# mcu.net
KiCad netlist of a schematic drawn in Altium Designer
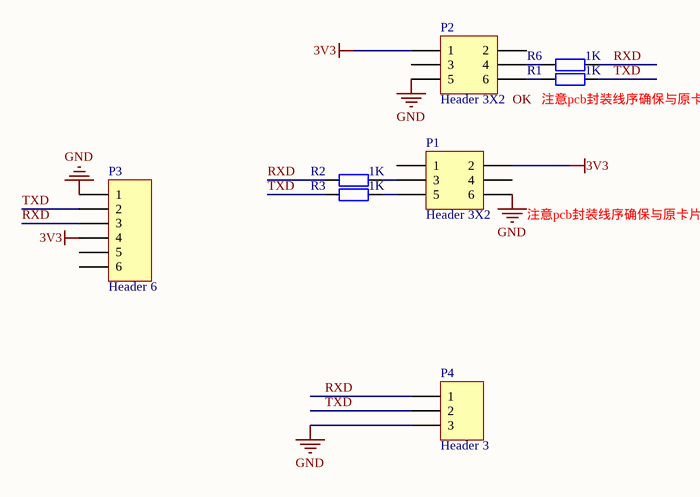
[diagram p0: mcu.SchDoc]

(export (version "E")
  (design (tool "Eeschema 10.0.6"))
  (components
    (comp (ref "P1")
      (value "Header 3X2")
      (footprint "3x2X2MM")
      (description "Header, 3-Pin, Dual row")
      (fields (field (name "PUBLISHER") "Altium Limited"))
      (libsource (lib "Miscellaneous Connectors") (part "Header 3X2"))
    )
    (comp (ref "P2")
      (value "Header 3X2")
      (footprint "3x2X2MM")
      (description "Header, 3-Pin, Dual row")
      (fields (field (name "PUBLISHER") "Altium Limited"))
      (libsource (lib "Miscellaneous Connectors") (part "Header 3X2"))
    )
    (comp (ref "P3")
      (value "Header 6")
      (footprint "5X2MMZ")
      (description "Header, 6-Pin")
      (fields (field (name "PUBLISHER") "Altium Limited"))
      (libsource (lib "Miscellaneous Connectors") (part "Header 6"))
    )
    (comp (ref "P4")
      (value "Header 3")
      (footprint "HDR1X3")
      (description "Header, 3-Pin")
      (fields (field (name "PUBLISHER") "Altium Limited"))
      (libsource (lib "Miscellaneous Connectors") (part "Header 3"))
    )
    (comp (ref "R1")
      (value "1K")
      (footprint "0603R")
      (description "Resistor")
      (fields (field (name "PUBLISHER") "Altium Limited"))
      (libsource (lib "Miscellaneous Devices") (part "Res2"))
    )
    (comp (ref "R2")
      (value "1K")
      (footprint "0603R")
      (description "Resistor")
      (fields (field (name "PUBLISHER") "Altium Limited"))
      (libsource (lib "Miscellaneous Devices") (part "Res2"))
    )
    (comp (ref "R3")
      (value "1K")
      (footprint "0603R")
      (description "Resistor")
      (fields (field (name "PUBLISHER") "Altium Limited"))
      (libsource (lib "Miscellaneous Devices") (part "Res2"))
    )
    (comp (ref "R6")
      (value "1K")
      (footprint "0603R")
      (description "Resistor")
      (fields (field (name "PUBLISHER") "Altium Limited"))
      (libsource (lib "Miscellaneous Devices") (part "Res2"))
    )
  )
  (nets
    (net (code "2") (name "/RXD") (class "Default")
      (node (ref "P3") (pin "3") (pinfunction "3_3") (pintype "passive"))
      (node (ref "P4") (pin "1") (pinfunction "1_1") (pintype "passive"))
      (node (ref "R2") (pin "2") (pinfunction "2_2") (pintype "passive"))
      (node (ref "R6") (pin "1") (pinfunction "1_1") (pintype "passive"))
    )
    (net (code "3") (name "/TXD") (class "Default")
      (node (ref "P3") (pin "2") (pinfunction "2_2") (pintype "passive"))
      (node (ref "P4") (pin "2") (pinfunction "2_2") (pintype "passive"))
      (node (ref "R1") (pin "1") (pinfunction "1_1") (pintype "passive"))
      (node (ref "R3") (pin "2") (pinfunction "2_2") (pintype "passive"))
    )
    (net (code "4") (name "3V3") (class "Default")
      (node (ref "P1") (pin "2") (pinfunction "2_2") (pintype "passive"))
      (node (ref "P2") (pin "1") (pinfunction "1_1") (pintype "passive"))
      (node (ref "P3") (pin "4") (pinfunction "4_4") (pintype "passive"))
    )
    (net (code "5") (name "GND") (class "Default")
      (node (ref "P1") (pin "6") (pinfunction "6_6") (pintype "passive"))
      (node (ref "P2") (pin "5") (pinfunction "5_5") (pintype "passive"))
      (node (ref "P3") (pin "1") (pinfunction "1_1") (pintype "passive"))
      (node (ref "P4") (pin "3") (pinfunction "3_3") (pintype "passive"))
    )
    (net (code "6") (name "Net-(P1-Pad3)") (class "Default")
      (node (ref "P1") (pin "3") (pinfunction "3_3") (pintype "passive"))
      (node (ref "R2") (pin "1") (pinfunction "1_1") (pintype "passive"))
    )
    (net (code "7") (name "Net-(P1-Pad5)") (class "Default")
      (node (ref "P1") (pin "5") (pinfunction "5_5") (pintype "passive"))
      (node (ref "R3") (pin "1") (pinfunction "1_1") (pintype "passive"))
    )
    (net (code "8") (name "Net-(P2-Pad4)") (class "Default")
      (node (ref "P2") (pin "4") (pinfunction "4_4") (pintype "passive"))
      (node (ref "R6") (pin "2") (pinfunction "2_2") (pintype "passive"))
    )
    (net (code "9") (name "Net-(P2-Pad6)") (class "Default")
      (node (ref "P2") (pin "6") (pinfunction "6_6") (pintype "passive"))
      (node (ref "R1") (pin "2") (pinfunction "2_2") (pintype "passive"))
    )
    (net (code "10") (name "unconnected-(P1-Pad1)") (class "Default")
      (node (ref "P1") (pin "1") (pinfunction "1_1") (pintype "passive"))
    )
    (net (code "11") (name "unconnected-(P1-Pad4)") (class "Default")
      (node (ref "P1") (pin "4") (pinfunction "4_4") (pintype "passive"))
    )
    (net (code "12") (name "unconnected-(P2-Pad2)") (class "Default")
      (node (ref "P2") (pin "2") (pinfunction "2_2") (pintype "passive"))
    )
    (net (code "13") (name "unconnected-(P2-Pad3)") (class "Default")
      (node (ref "P2") (pin "3") (pinfunction "3_3") (pintype "passive"))
    )
    (net (code "14") (name "unconnected-(P3-Pad5)") (class "Default")
      (node (ref "P3") (pin "5") (pinfunction "5_5") (pintype "passive"))
    )
    (net (code "15") (name "unconnected-(P3-Pad6)") (class "Default")
      (node (ref "P3") (pin "6") (pinfunction "6_6") (pintype "passive"))
    )
  )
)
